# MainSocket.net
KiCad netlist of a schematic drawn in Altium Designer
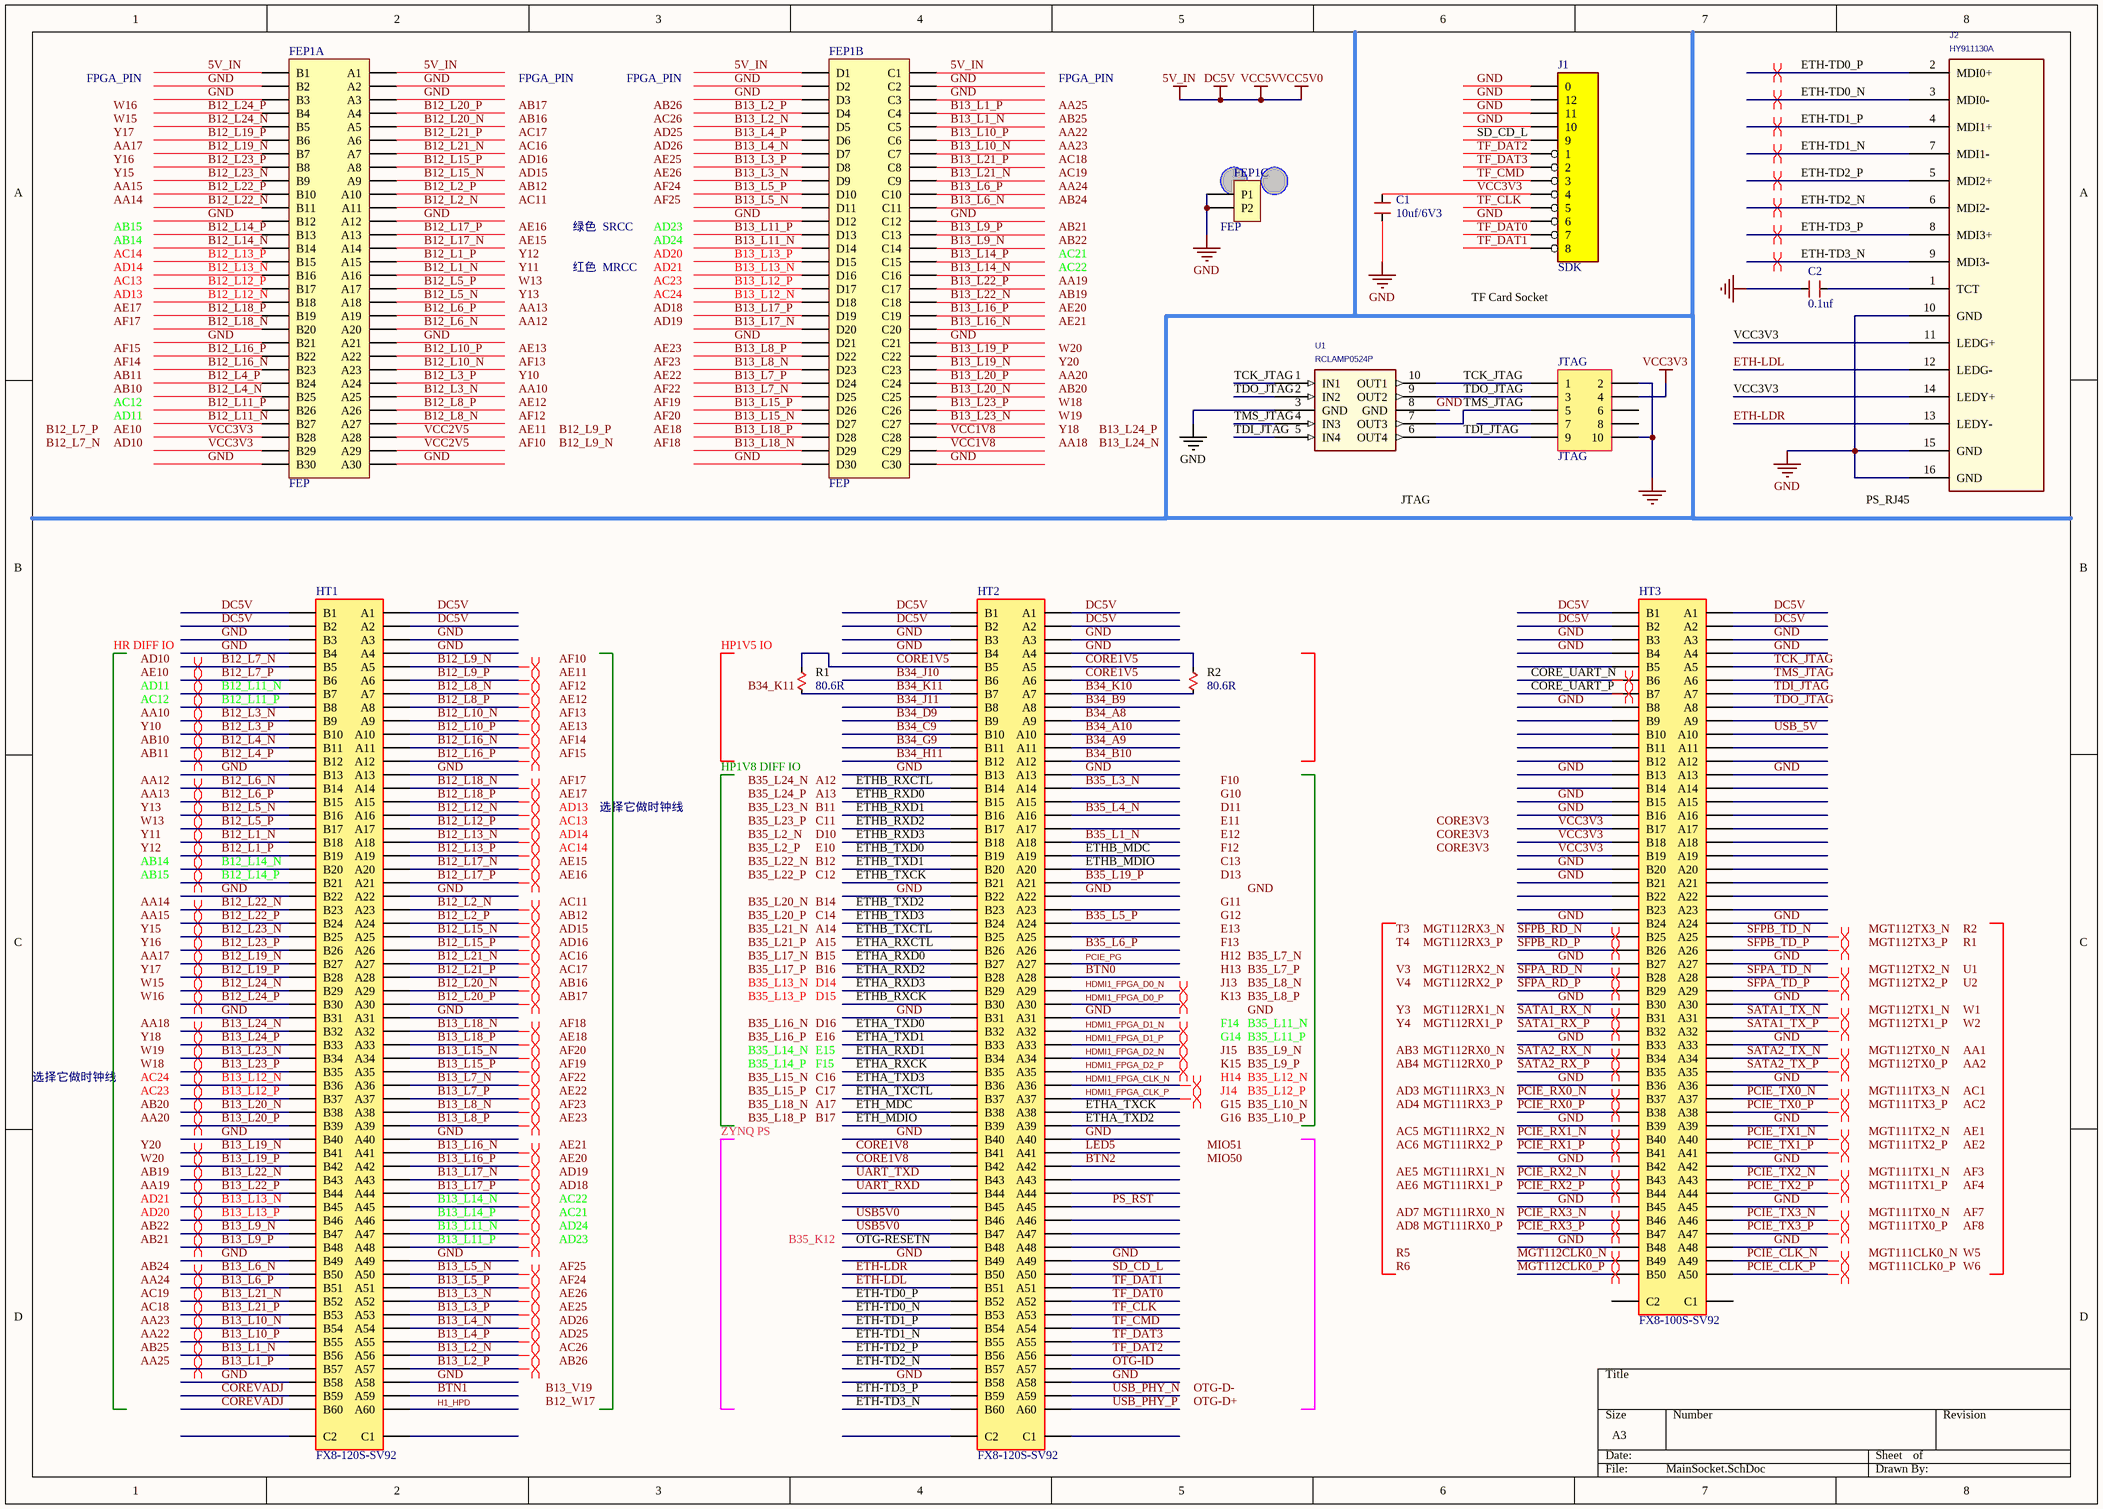
[diagram p0: MainSocket.SchDoc]

(export (version "E")
  (design (tool "Eeschema 10.0.6"))
  (components
    (comp (ref "C1")
      (value "10uf/6V3")
      (footprint "CAP0603")
      (description "Generic Capacitor")
      (libsource (lib "Digilent") (part "CAPACITOR"))
    )
    (comp (ref "C2")
      (value "0.1uf")
      (footprint "CAP0402")
      (description "Generic Capacitor")
      (libsource (lib "Miz701_fun20160215") (part "CAPACITOR"))
    )
    (comp (ref "FEP1") (value "FEP") (footprint "FEP-X2") (libsource (lib "") (part "FEP-2X_1")))
    (comp (ref "HT1")
      (value "FX8-120S-SV92")
      (footprint "FX8-120S-SV92")
      (libsource (lib "MIZ7035") (part "FX8-120P-SV92"))
    )
    (comp (ref "HT2")
      (value "FX8-120S-SV92")
      (footprint "FX8-120S-SV92")
      (libsource (lib "MIZ7035") (part "FX8-120P-SV92"))
    )
    (comp (ref "HT3")
      (value "FX8-100S-SV92")
      (footprint "FX8-100S-SV92")
      (libsource (lib "MIZ7035") (part "FX8-100P-SV92"))
    )
    (comp (ref "J1") (value "SDK") (footprint "TF_K") (libsource (lib "jinrylib") (part "SD")))
    (comp (ref "J2") (value "HY911130A") (footprint "HY911130A") (libsource (lib "*") (part "HY911130A")))
    (comp (ref "JTAG")
      (value "JTAG")
      (footprint "HEADER5X2X2.0T")
      (libsource (lib "mis607") (part "HEADER2X5"))
    )
    (comp (ref "R1")
      (value "80.6R")
      (footprint "RES0402")
      (description "Generic Resistor")
      (libsource (lib "MIZ7035_定制") (part "RESISTOR"))
    )
    (comp (ref "R2")
      (value "80.6R")
      (footprint "RES0402")
      (description "Generic Resistor")
      (libsource (lib "MIZ7035_定制") (part "RESISTOR"))
    )
    (comp (ref "U1")
      (value "RCLAMP0524P")
      (footprint "SLP2510P8_10")
      (libsource (lib "*") (part "RCLAMP0524P"))
    )
  )
  (nets
    (net (code "109") (name "/B12_L1_N") (class "Default")
      (node (ref "FEP1") (pin "A16") (pinfunction "A16_A16") (pintype "passive"))
      (node (ref "HT1") (pin "B18") (pinfunction "B18_B18") (pintype "passive"))
    )
    (net (code "110") (name "/B12_L1_P") (class "Default")
      (node (ref "FEP1") (pin "A15") (pinfunction "A15_A15") (pintype "passive"))
      (node (ref "HT1") (pin "B19") (pinfunction "B19_B19") (pintype "passive"))
    )
    (net (code "111") (name "/B12_L2_N") (class "Default")
      (node (ref "FEP1") (pin "A11") (pinfunction "A11_A11") (pintype "passive"))
      (node (ref "HT1") (pin "A23") (pinfunction "A23_A23") (pintype "passive"))
    )
    (net (code "112") (name "/B12_L2_P") (class "Default")
      (node (ref "FEP1") (pin "A10") (pinfunction "A10_A10") (pintype "passive"))
      (node (ref "HT1") (pin "A24") (pinfunction "A24_A24") (pintype "passive"))
    )
    (net (code "113") (name "/B12_L3_N") (class "Default")
      (node (ref "FEP1") (pin "A25") (pinfunction "A25_A25") (pintype "passive"))
      (node (ref "HT1") (pin "B9") (pinfunction "B9_B9") (pintype "passive"))
    )
    (net (code "114") (name "/B12_L3_P") (class "Default")
      (node (ref "FEP1") (pin "A24") (pinfunction "A24_A24") (pintype "passive"))
      (node (ref "HT1") (pin "B10") (pinfunction "B10_B10") (pintype "passive"))
    )
    (net (code "115") (name "/B12_L4_N") (class "Default")
      (node (ref "FEP1") (pin "B25") (pinfunction "B25_B25") (pintype "passive"))
      (node (ref "HT1") (pin "B11") (pinfunction "B11_B11") (pintype "passive"))
    )
    (net (code "116") (name "/B12_L4_P") (class "Default")
      (node (ref "FEP1") (pin "B24") (pinfunction "B24_B24") (pintype "passive"))
      (node (ref "HT1") (pin "B12") (pinfunction "B12_B12") (pintype "passive"))
    )
    (net (code "117") (name "/B12_L5_N") (class "Default")
      (node (ref "FEP1") (pin "A18") (pinfunction "A18_A18") (pintype "passive"))
      (node (ref "HT1") (pin "B16") (pinfunction "B16_B16") (pintype "passive"))
    )
    (net (code "118") (name "/B12_L5_P") (class "Default")
      (node (ref "FEP1") (pin "A17") (pinfunction "A17_A17") (pintype "passive"))
      (node (ref "HT1") (pin "B17") (pinfunction "B17_B17") (pintype "passive"))
    )
    (net (code "119") (name "/B12_L6_N") (class "Default")
      (node (ref "FEP1") (pin "A20") (pinfunction "A20_A20") (pintype "passive"))
      (node (ref "HT1") (pin "B14") (pinfunction "B14_B14") (pintype "passive"))
    )
    (net (code "120") (name "/B12_L6_P") (class "Default")
      (node (ref "FEP1") (pin "A19") (pinfunction "A19_A19") (pintype "passive"))
      (node (ref "HT1") (pin "B15") (pinfunction "B15_B15") (pintype "passive"))
    )
    (net (code "121") (name "/B12_L7_N") (class "Default")
      (node (ref "HT1") (pin "B5") (pinfunction "B5_B5") (pintype "passive"))
    )
    (net (code "122") (name "/B12_L7_P") (class "Default")
      (node (ref "HT1") (pin "B6") (pinfunction "B6_B6") (pintype "passive"))
    )
    (net (code "123") (name "/B12_L8_N") (class "Default")
      (node (ref "FEP1") (pin "A27") (pinfunction "A27_A27") (pintype "passive"))
      (node (ref "HT1") (pin "A7") (pinfunction "A7_A7") (pintype "passive"))
    )
    (net (code "124") (name "/B12_L8_P") (class "Default")
      (node (ref "FEP1") (pin "A26") (pinfunction "A26_A26") (pintype "passive"))
      (node (ref "HT1") (pin "A8") (pinfunction "A8_A8") (pintype "passive"))
    )
    (net (code "125") (name "/B12_L9_N") (class "Default")
      (node (ref "HT1") (pin "A5") (pinfunction "A5_A5") (pintype "passive"))
    )
    (net (code "126") (name "/B12_L9_P") (class "Default")
      (node (ref "HT1") (pin "A6") (pinfunction "A6_A6") (pintype "passive"))
    )
    (net (code "127") (name "/B12_L10_N") (class "Default")
      (node (ref "FEP1") (pin "A23") (pinfunction "A23_A23") (pintype "passive"))
      (node (ref "HT1") (pin "A9") (pinfunction "A9_A9") (pintype "passive"))
    )
    (net (code "128") (name "/B12_L10_P") (class "Default")
      (node (ref "FEP1") (pin "A22") (pinfunction "A22_A22") (pintype "passive"))
      (node (ref "HT1") (pin "A10") (pinfunction "A10_A10") (pintype "passive"))
    )
    (net (code "129") (name "/B12_L11_N") (class "Default")
      (node (ref "FEP1") (pin "B27") (pinfunction "B27_B27") (pintype "passive"))
      (node (ref "HT1") (pin "B7") (pinfunction "B7_B7") (pintype "passive"))
    )
    (net (code "130") (name "/B12_L11_P") (class "Default")
      (node (ref "FEP1") (pin "B26") (pinfunction "B26_B26") (pintype "passive"))
      (node (ref "HT1") (pin "B8") (pinfunction "B8_B8") (pintype "passive"))
    )
    (net (code "131") (name "/B12_L12_N") (class "Default")
      (node (ref "FEP1") (pin "B18") (pinfunction "B18_B18") (pintype "passive"))
      (node (ref "HT1") (pin "A16") (pinfunction "A16_A16") (pintype "passive"))
    )
    (net (code "132") (name "/B12_L12_P") (class "Default")
      (node (ref "FEP1") (pin "B17") (pinfunction "B17_B17") (pintype "passive"))
      (node (ref "HT1") (pin "A17") (pinfunction "A17_A17") (pintype "passive"))
    )
    (net (code "133") (name "/B12_L13_N") (class "Default")
      (node (ref "FEP1") (pin "B16") (pinfunction "B16_B16") (pintype "passive"))
      (node (ref "HT1") (pin "A18") (pinfunction "A18_A18") (pintype "passive"))
    )
    (net (code "134") (name "/B12_L13_P") (class "Default")
      (node (ref "FEP1") (pin "B15") (pinfunction "B15_B15") (pintype "passive"))
      (node (ref "HT1") (pin "A19") (pinfunction "A19_A19") (pintype "passive"))
    )
    (net (code "135") (name "/B12_L14_N") (class "Default")
      (node (ref "FEP1") (pin "B14") (pinfunction "B14_B14") (pintype "passive"))
      (node (ref "HT1") (pin "B20") (pinfunction "B20_B20") (pintype "passive"))
    )
    (net (code "136") (name "/B12_L14_P") (class "Default")
      (node (ref "FEP1") (pin "B13") (pinfunction "B13_B13") (pintype "passive"))
      (node (ref "HT1") (pin "B21") (pinfunction "B21_B21") (pintype "passive"))
    )
    (net (code "137") (name "/B12_L15_N") (class "Default")
      (node (ref "FEP1") (pin "A9") (pinfunction "A9_A9") (pintype "passive"))
      (node (ref "HT1") (pin "A25") (pinfunction "A25_A25") (pintype "passive"))
    )
    (net (code "138") (name "/B12_L15_P") (class "Default")
      (node (ref "FEP1") (pin "A8") (pinfunction "A8_A8") (pintype "passive"))
      (node (ref "HT1") (pin "A26") (pinfunction "A26_A26") (pintype "passive"))
    )
    (net (code "139") (name "/B12_L16_N") (class "Default")
      (node (ref "FEP1") (pin "B23") (pinfunction "B23_B23") (pintype "passive"))
      (node (ref "HT1") (pin "A11") (pinfunction "A11_A11") (pintype "passive"))
    )
    (net (code "140") (name "/B12_L16_P") (class "Default")
      (node (ref "FEP1") (pin "B22") (pinfunction "B22_B22") (pintype "passive"))
      (node (ref "HT1") (pin "A12") (pinfunction "A12_A12") (pintype "passive"))
    )
    (net (code "141") (name "/B12_L17_N") (class "Default")
      (node (ref "FEP1") (pin "A14") (pinfunction "A14_A14") (pintype "passive"))
      (node (ref "HT1") (pin "A20") (pinfunction "A20_A20") (pintype "passive"))
    )
    (net (code "142") (name "/B12_L17_P") (class "Default")
      (node (ref "FEP1") (pin "A13") (pinfunction "A13_A13") (pintype "passive"))
      (node (ref "HT1") (pin "A21") (pinfunction "A21_A21") (pintype "passive"))
    )
    (net (code "143") (name "/B12_L18_N") (class "Default")
      (node (ref "FEP1") (pin "B20") (pinfunction "B20_B20") (pintype "passive"))
      (node (ref "HT1") (pin "A14") (pinfunction "A14_A14") (pintype "passive"))
    )
    (net (code "144") (name "/B12_L18_P") (class "Default")
      (node (ref "FEP1") (pin "B19") (pinfunction "B19_B19") (pintype "passive"))
      (node (ref "HT1") (pin "A15") (pinfunction "A15_A15") (pintype "passive"))
    )
    (net (code "145") (name "/B12_L19_N") (class "Default")
      (node (ref "FEP1") (pin "B7") (pinfunction "B7_B7") (pintype "passive"))
      (node (ref "HT1") (pin "B27") (pinfunction "B27_B27") (pintype "passive"))
    )
    (net (code "146") (name "/B12_L19_P") (class "Default")
      (node (ref "FEP1") (pin "B6") (pinfunction "B6_B6") (pintype "passive"))
      (node (ref "HT1") (pin "B28") (pinfunction "B28_B28") (pintype "passive"))
    )
    (net (code "147") (name "/B12_L20_N") (class "Default")
      (node (ref "FEP1") (pin "A5") (pinfunction "A5_A5") (pintype "passive"))
      (node (ref "HT1") (pin "A29") (pinfunction "A29_A29") (pintype "passive"))
    )
    (net (code "148") (name "/B12_L20_P") (class "Default")
      (node (ref "FEP1") (pin "A4") (pinfunction "A4_A4") (pintype "passive"))
      (node (ref "HT1") (pin "A30") (pinfunction "A30_A30") (pintype "passive"))
    )
    (net (code "149") (name "/B12_L21_N") (class "Default")
      (node (ref "FEP1") (pin "A7") (pinfunction "A7_A7") (pintype "passive"))
      (node (ref "HT1") (pin "A27") (pinfunction "A27_A27") (pintype "passive"))
    )
    (net (code "150") (name "/B12_L21_P") (class "Default")
      (node (ref "FEP1") (pin "A6") (pinfunction "A6_A6") (pintype "passive"))
      (node (ref "HT1") (pin "A28") (pinfunction "A28_A28") (pintype "passive"))
    )
    (net (code "151") (name "/B12_L22_N") (class "Default")
      (node (ref "FEP1") (pin "B11") (pinfunction "B11_B11") (pintype "passive"))
      (node (ref "HT1") (pin "B23") (pinfunction "B23_B23") (pintype "passive"))
    )
    (net (code "152") (name "/B12_L22_P") (class "Default")
      (node (ref "FEP1") (pin "B10") (pinfunction "B10_B10") (pintype "passive"))
      (node (ref "HT1") (pin "B24") (pinfunction "B24_B24") (pintype "passive"))
    )
    (net (code "153") (name "/B12_L23_N") (class "Default")
      (node (ref "FEP1") (pin "B9") (pinfunction "B9_B9") (pintype "passive"))
      (node (ref "HT1") (pin "B25") (pinfunction "B25_B25") (pintype "passive"))
    )
    (net (code "154") (name "/B12_L23_P") (class "Default")
      (node (ref "FEP1") (pin "B8") (pinfunction "B8_B8") (pintype "passive"))
      (node (ref "HT1") (pin "B26") (pinfunction "B26_B26") (pintype "passive"))
    )
    (net (code "155") (name "/B12_L24_N") (class "Default")
      (node (ref "FEP1") (pin "B5") (pinfunction "B5_B5") (pintype "passive"))
      (node (ref "HT1") (pin "B29") (pinfunction "B29_B29") (pintype "passive"))
    )
    (net (code "156") (name "/B12_L24_P") (class "Default")
      (node (ref "FEP1") (pin "B4") (pinfunction "B4_B4") (pintype "passive"))
      (node (ref "HT1") (pin "B30") (pinfunction "B30_B30") (pintype "passive"))
    )
    (net (code "158") (name "/B13_L1_N") (class "Default")
      (node (ref "FEP1") (pin "C5") (pinfunction "C5_C5") (pintype "passive"))
      (node (ref "HT1") (pin "B56") (pinfunction "B56_B56") (pintype "passive"))
    )
    (net (code "159") (name "/B13_L1_P") (class "Default")
      (node (ref "FEP1") (pin "C4") (pinfunction "C4_C4") (pintype "passive"))
      (node (ref "HT1") (pin "B57") (pinfunction "B57_B57") (pintype "passive"))
    )
    (net (code "160") (name "/B13_L2_N") (class "Default")
      (node (ref "FEP1") (pin "D5") (pinfunction "D5_D5") (pintype "passive"))
      (node (ref "HT1") (pin "A56") (pinfunction "A56_A56") (pintype "passive"))
    )
    (net (code "161") (name "/B13_L2_P") (class "Default")
      (node (ref "FEP1") (pin "D4") (pinfunction "D4_D4") (pintype "passive"))
      (node (ref "HT1") (pin "A57") (pinfunction "A57_A57") (pintype "passive"))
    )
    (net (code "162") (name "/B13_L3_N") (class "Default")
      (node (ref "FEP1") (pin "D9") (pinfunction "D9_D9") (pintype "passive"))
      (node (ref "HT1") (pin "A52") (pinfunction "A52_A52") (pintype "passive"))
    )
    (net (code "163") (name "/B13_L3_P") (class "Default")
      (node (ref "FEP1") (pin "D8") (pinfunction "D8_D8") (pintype "passive"))
      (node (ref "HT1") (pin "A53") (pinfunction "A53_A53") (pintype "passive"))
    )
    (net (code "164") (name "/B13_L4_N") (class "Default")
      (node (ref "FEP1") (pin "D7") (pinfunction "D7_D7") (pintype "passive"))
      (node (ref "HT1") (pin "A54") (pinfunction "A54_A54") (pintype "passive"))
    )
    (net (code "165") (name "/B13_L4_P") (class "Default")
      (node (ref "FEP1") (pin "D6") (pinfunction "D6_D6") (pintype "passive"))
      (node (ref "HT1") (pin "A55") (pinfunction "A55_A55") (pintype "passive"))
    )
    (net (code "166") (name "/B13_L5_N") (class "Default")
      (node (ref "FEP1") (pin "D11") (pinfunction "D11_D11") (pintype "passive"))
      (node (ref "HT1") (pin "A50") (pinfunction "A50_A50") (pintype "passive"))
    )
    (net (code "167") (name "/B13_L5_P") (class "Default")
      (node (ref "FEP1") (pin "D10") (pinfunction "D10_D10") (pintype "passive"))
      (node (ref "HT1") (pin "A51") (pinfunction "A51_A51") (pintype "passive"))
    )
    (net (code "168") (name "/B13_L6_N") (class "Default")
      (node (ref "FEP1") (pin "C11") (pinfunction "C11_C11") (pintype "passive"))
      (node (ref "HT1") (pin "B50") (pinfunction "B50_B50") (pintype "passive"))
    )
    (net (code "169") (name "/B13_L6_P") (class "Default")
      (node (ref "FEP1") (pin "C10") (pinfunction "C10_C10") (pintype "passive"))
      (node (ref "HT1") (pin "B51") (pinfunction "B51_B51") (pintype "passive"))
    )
    (net (code "170") (name "/B13_L7_N") (class "Default")
      (node (ref "FEP1") (pin "D25") (pinfunction "D25_D25") (pintype "passive"))
      (node (ref "HT1") (pin "A36") (pinfunction "A36_A36") (pintype "passive"))
    )
    (net (code "171") (name "/B13_L7_P") (class "Default")
      (node (ref "FEP1") (pin "D24") (pinfunction "D24_D24") (pintype "passive"))
      (node (ref "HT1") (pin "A37") (pinfunction "A37_A37") (pintype "passive"))
    )
    (net (code "172") (name "/B13_L8_N") (class "Default")
      (node (ref "FEP1") (pin "D23") (pinfunction "D23_D23") (pintype "passive"))
      (node (ref "HT1") (pin "A38") (pinfunction "A38_A38") (pintype "passive"))
    )
    (net (code "173") (name "/B13_L8_P") (class "Default")
      (node (ref "FEP1") (pin "D22") (pinfunction "D22_D22") (pintype "passive"))
      (node (ref "HT1") (pin "A39") (pinfunction "A39_A39") (pintype "passive"))
    )
    (net (code "174") (name "/B13_L9_N") (class "Default")
      (node (ref "FEP1") (pin "C14") (pinfunction "C14_C14") (pintype "passive"))
      (node (ref "HT1") (pin "B47") (pinfunction "B47_B47") (pintype "passive"))
    )
    (net (code "175") (name "/B13_L9_P") (class "Default")
      (node (ref "FEP1") (pin "C13") (pinfunction "C13_C13") (pintype "passive"))
      (node (ref "HT1") (pin "B48") (pinfunction "B48_B48") (pintype "passive"))
    )
    (net (code "176") (name "/B13_L10_N") (class "Default")
      (node (ref "FEP1") (pin "C7") (pinfunction "C7_C7") (pintype "passive"))
      (node (ref "HT1") (pin "B54") (pinfunction "B54_B54") (pintype "passive"))
    )
    (net (code "177") (name "/B13_L10_P") (class "Default")
      (node (ref "FEP1") (pin "C6") (pinfunction "C6_C6") (pintype "passive"))
      (node (ref "HT1") (pin "B55") (pinfunction "B55_B55") (pintype "passive"))
    )
    (net (code "178") (name "/B13_L11_N") (class "Default")
      (node (ref "FEP1") (pin "D14") (pinfunction "D14_D14") (pintype "passive"))
      (node (ref "HT1") (pin "A47") (pinfunction "A47_A47") (pintype "passive"))
    )
    (net (code "179") (name "/B13_L11_P") (class "Default")
      (node (ref "FEP1") (pin "D13") (pinfunction "D13_D13") (pintype "passive"))
      (node (ref "HT1") (pin "A48") (pinfunction "A48_A48") (pintype "passive"))
    )
    (net (code "180") (name "/B13_L12_N") (class "Default")
      (node (ref "FEP1") (pin "D18") (pinfunction "D18_D18") (pintype "passive"))
      (node (ref "HT1") (pin "B36") (pinfunction "B36_B36") (pintype "passive"))
    )
    (net (code "181") (name "/B13_L12_P") (class "Default")
      (node (ref "FEP1") (pin "D17") (pinfunction "D17_D17") (pintype "passive"))
      (node (ref "HT1") (pin "B37") (pinfunction "B37_B37") (pintype "passive"))
    )
    (net (code "182") (name "/B13_L13_N") (class "Default")
      (node (ref "FEP1") (pin "D16") (pinfunction "D16_D16") (pintype "passive"))
      (node (ref "HT1") (pin "B45") (pinfunction "B45_B45") (pintype "passive"))
    )
    (net (code "183") (name "/B13_L13_P") (class "Default")
      (node (ref "FEP1") (pin "D15") (pinfunction "D15_D15") (pintype "passive"))
      (node (ref "HT1") (pin "B46") (pinfunction "B46_B46") (pintype "passive"))
    )
    (net (code "184") (name "/B13_L14_N") (class "Default")
      (node (ref "FEP1") (pin "C16") (pinfunction "C16_C16") (pintype "passive"))
      (node (ref "HT1") (pin "A45") (pinfunction "A45_A45") (pintype "passive"))
    )
    (net (code "185") (name "/B13_L14_P") (class "Default")
      (node (ref "FEP1") (pin "C15") (pinfunction "C15_C15") (pintype "passive"))
      (node (ref "HT1") (pin "A46") (pinfunction "A46_A46") (pintype "passive"))
    )
    (net (code "186") (name "/B13_L15_N") (class "Default")
      (node (ref "FEP1") (pin "D27") (pinfunction "D27_D27") (pintype "passive"))
      (node (ref "HT1") (pin "A34") (pinfunction "A34_A34") (pintype "passive"))
    )
    (net (code "187") (name "/B13_L15_P") (class "Default")
      (node (ref "FEP1") (pin "D26") (pinfunction "D26_D26") (pintype "passive"))
      (node (ref "HT1") (pin "A35") (pinfunction "A35_A35") (pintype "passive"))
    )
    (net (code "188") (name "/B13_L16_N") (class "Default")
      (node (ref "FEP1") (pin "C20") (pinfunction "C20_C20") (pintype "passive"))
      (node (ref "HT1") (pin "A41") (pinfunction "A41_A41") (pintype "passive"))
    )
    (net (code "189") (name "/B13_L16_P") (class "Default")
      (node (ref "FEP1") (pin "C19") (pinfunction "C19_C19") (pintype "passive"))
      (node (ref "HT1") (pin "A42") (pinfunction "A42_A42") (pintype "passive"))
    )
    (net (code "190") (name "/B13_L17_N") (class "Default")
      (node (ref "FEP1") (pin "D20") (pinfunction "D20_D20") (pintype "passive"))
      (node (ref "HT1") (pin "A43") (pinfunction "A43_A43") (pintype "passive"))
    )
    (net (code "191") (name "/B13_L17_P") (class "Default")
      (node (ref "FEP1") (pin "D19") (pinfunction "D19_D19") (pintype "passive"))
      (node (ref "HT1") (pin "A44") (pinfunction "A44_A44") (pintype "passive"))
    )
    (net (code "192") (name "/B13_L18_N") (class "Default")
      (node (ref "FEP1") (pin "D29") (pinfunction "D29_D29") (pintype "passive"))
      (node (ref "HT1") (pin "A32") (pinfunction "A32_A32") (pintype "passive"))
    )
    (net (code "193") (name "/B13_L18_P") (class "Default")
      (node (ref "FEP1") (pin "D28") (pinfunction "D28_D28") (pintype "passive"))
      (node (ref "HT1") (pin "A33") (pinfunction "A33_A33") (pintype "passive"))
    )
    (net (code "194") (name "/B13_L19_N") (class "Default")
      (node (ref "FEP1") (pin "C23") (pinfunction "C23_C23") (pintype "passive"))
      (node (ref "HT1") (pin "B41") (pinfunction "B41_B41") (pintype "passive"))
    )
    (net (code "195") (name "/B13_L19_P") (class "Default")
      (node (ref "FEP1") (pin "C22") (pinfunction "C22_C22") (pintype "passive"))
      (node (ref "HT1") (pin "B42") (pinfunction "B42_B42") (pintype "passive"))
    )
    (net (code "196") (name "/B13_L20_N") (class "Default")
      (node (ref "FEP1") (pin "C25") (pinfunction "C25_C25") (pintype "passive"))
      (node (ref "HT1") (pin "B38") (pinfunction "B38_B38") (pintype "passive"))
    )
    (net (code "197") (name "/B13_L20_P") (class "Default")
      (node (ref "FEP1") (pin "C24") (pinfunction "C24_C24") (pintype "passive"))
      (node (ref "HT1") (pin "B39") (pinfunction "B39_B39") (pintype "passive"))
    )
    (net (code "198") (name "/B13_L21_N") (class "Default")
      (node (ref "FEP1") (pin "C9") (pinfunction "C9_C9") (pintype "passive"))
      (node (ref "HT1") (pin "B52") (pinfunction "B52_B52") (pintype "passive"))
    )
    (net (code "199") (name "/B13_L21_P") (class "Default")
      (node (ref "FEP1") (pin "C8") (pinfunction "C8_C8") (pintype "passive"))
      (node (ref "HT1") (pin "B53") (pinfunction "B53_B53") (pintype "passive"))
    )
    (net (code "200") (name "/B13_L22_N") (class "Default")
      (node (ref "FEP1") (pin "C18") (pinfunction "C18_C18") (pintype "passive"))
      (node (ref "HT1") (pin "B43") (pinfunction "B43_B43") (pintype "passive"))
    )
    (net (code "201") (name "/B13_L22_P") (class "Default")
      (node (ref "FEP1") (pin "C17") (pinfunction "C17_C17") (pintype "passive"))
      (node (ref "HT1") (pin "B44") (pinfunction "B44_B44") (pintype "passive"))
    )
    (net (code "202") (name "/B13_L23_N") (class "Default")
      (node (ref "FEP1") (pin "C27") (pinfunction "C27_C27") (pintype "passive"))
      (node (ref "HT1") (pin "B34") (pinfunction "B34_B34") (pintype "passive"))
    )
    (net (code "203") (name "/B13_L23_P") (class "Default")
      (node (ref "FEP1") (pin "C26") (pinfunction "C26_C26") (pintype "passive"))
      (node (ref "HT1") (pin "B35") (pinfunction "B35_B35") (pintype "passive"))
    )
    (net (code "204") (name "/B13_L24_N") (class "Default")
      (node (ref "HT1") (pin "B32") (pinfunction "B32_B32") (pintype "passive"))
    )
    (net (code "205") (name "/B13_L24_P") (class "Default")
      (node (ref "HT1") (pin "B33") (pinfunction "B33_B33") (pintype "passive"))
    )
    (net (code "211") (name "/B34_A8") (class "Default")
      (node (ref "HT2") (pin "A9") (pinfunction "A9_A9") (pintype "passive"))
    )
    (net (code "212") (name "/B34_A9") (class "Default")
      (node (ref "HT2") (pin "A11") (pinfunction "A11_A11") (pintype "passive"))
    )
    (net (code "213") (name "/B34_A10") (class "Default")
      (node (ref "HT2") (pin "A10") (pinfunction "A10_A10") (pintype "passive"))
    )
    (net (code "214") (name "/B34_B9") (class "Default")
      (node (ref "HT2") (pin "A8") (pinfunction "A8_A8") (pintype "passive"))
    )
    (net (code "215") (name "/B34_B10") (class "Default")
      (node (ref "HT2") (pin "A12") (pinfunction "A12_A12") (pintype "passive"))
    )
    (net (code "216") (name "/B34_C9") (class "Default")
      (node (ref "HT2") (pin "B10") (pinfunction "B10_B10") (pintype "passive"))
    )
    (net (code "217") (name "/B34_D9") (class "Default")
      (node (ref "HT2") (pin "B9") (pinfunction "B9_B9") (pintype "passive"))
    )
    (net (code "218") (name "/B34_G9") (class "Default")
      (node (ref "HT2") (pin "B11") (pinfunction "B11_B11") (pintype "passive"))
    )
    (net (code "219") (name "/B34_H11") (class "Default")
      (node (ref "HT2") (pin "B12") (pinfunction "B12_B12") (pintype "passive"))
    )
    (net (code "220") (name "/B34_J10") (class "Default")
      (node (ref "HT2") (pin "B6") (pinfunction "B6_B6") (pintype "passive"))
    )
    (net (code "221") (name "/B34_J11") (class "Default")
      (node (ref "HT2") (pin "B8") (pinfunction "B8_B8") (pintype "passive"))
    )
    (net (code "222") (name "/B34_K10") (class "Default")
      (node (ref "HT2") (pin "A7") (pinfunction "A7_A7") (pintype "passive"))
      (node (ref "R2") (pin "1") (pinfunction "1_1") (pintype "passive"))
    )
    (net (code "223") (name "/B34_K11") (class "Default")
      (node (ref "HT2") (pin "B7") (pinfunction "B7_B7") (pintype "passive"))
      (node (ref "R1") (pin "1") (pinfunction "1_1") (pintype "passive"))
    )
    (net (code "225") (name "/B35_L1_N") (class "Default")
      (node (ref "HT2") (pin "A18") (pinfunction "A18_A18") (pintype "passive"))
    )
    (net (code "228") (name "/B35_L3_N") (class "Default")
      (node (ref "HT2") (pin "A14") (pinfunction "A14_A14") (pintype "passive"))
    )
    (net (code "229") (name "/B35_L4_N") (class "Default")
      (node (ref "HT2") (pin "A16") (pinfunction "A16_A16") (pintype "passive"))
    )
    (net (code "230") (name "/B35_L5_P") (class "Default")
      (node (ref "HT2") (pin "A24") (pinfunction "A24_A24") (pintype "passive"))
    )
    (net (code "231") (name "/B35_L6_P") (class "Default")
      (node (ref "HT2") (pin "A26") (pinfunction "A26_A26") (pintype "passive"))
    )
    (net (code "256") (name "/B35_L19_P") (class "Default")
      (node (ref "HT2") (pin "A21") (pinfunction "A21_A21") (pintype "passive"))
    )
    (net (code "267") (name "/BTN0") (class "Default")
      (node (ref "HT2") (pin "A28") (pinfunction "A28_A28") (pintype "passive"))
    )
    (net (code "268") (name "/BTN1") (class "Default")
      (node (ref "HT1") (pin "A59") (pinfunction "A59_A59") (pintype "passive"))
    )
    (net (code "269") (name "/BTN2") (class "Default")
      (node (ref "HT2") (pin "A42") (pinfunction "A42_A42") (pintype "passive"))
    )
    (net (code "276") (name "/CORE1V5") (class "Default")
      (node (ref "HT2") (pin "A5") (pinfunction "A5_A5") (pintype "passive"))
      (node (ref "HT2") (pin "A6") (pinfunction "A6_A6") (pintype "passive"))
      (node (ref "HT2") (pin "B5") (pinfunction "B5_B5") (pintype "passive"))
      (node (ref "R1") (pin "2") (pinfunction "2_2") (pintype "passive"))
    )
    (net (code "277") (name "/CORE1V8") (class "Default")
      (node (ref "HT2") (pin "B41") (pinfunction "B41_B41") (pintype "passive"))
      (node (ref "HT2") (pin "B42") (pinfunction "B42_B42") (pintype "passive"))
    )
    (net (code "279") (name "/COREVADJ") (class "Default")
      (node (ref "HT1") (pin "B59") (pinfunction "B59_B59") (pintype "passive"))
      (node (ref "HT1") (pin "B60") (pinfunction "B60_B60") (pintype "passive"))
    )
    (net (code "280") (name "/CORE_UART_N") (class "Default")
      (node (ref "HT3") (pin "B6") (pinfunction "B6_B6") (pintype "passive"))
    )
    (net (code "281") (name "/CORE_UART_P") (class "Default")
      (node (ref "HT3") (pin "B7") (pinfunction "B7_B7") (pintype "passive"))
    )
    (net (code "294") (name "/ETH-LDL") (class "Default")
      (node (ref "HT2") (pin "B51") (pinfunction "B51_B51") (pintype "passive"))
      (node (ref "J2") (pin "12") (pinfunction "LEDG-_12") (pintype "passive"))
    )
    (net (code "295") (name "/ETH-LDR") (class "Default")
      (node (ref "HT2") (pin "B50") (pinfunction "B50_B50") (pintype "passive"))
      (node (ref "J2") (pin "13") (pinfunction "LEDY-_13") (pintype "passive"))
    )
    (net (code "296") (name "/ETH-TD0_N") (class "Default")
      (node (ref "HT2") (pin "B53") (pinfunction "B53_B53") (pintype "passive"))
      (node (ref "J2") (pin "3") (pinfunction "MDI0-_3") (pintype "passive"))
    )
    (net (code "297") (name "/ETH-TD0_P") (class "Default")
      (node (ref "HT2") (pin "B52") (pinfunction "B52_B52") (pintype "passive"))
      (node (ref "J2") (pin "2") (pinfunction "MDI0+_2") (pintype "passive"))
    )
    (net (code "298") (name "/ETH-TD1_N") (class "Default")
      (node (ref "HT2") (pin "B55") (pinfunction "B55_B55") (pintype "passive"))
      (node (ref "J2") (pin "7") (pinfunction "MDI1-_7") (pintype "passive"))
    )
    (net (code "299") (name "/ETH-TD1_P") (class "Default")
      (node (ref "HT2") (pin "B54") (pinfunction "B54_B54") (pintype "passive"))
      (node (ref "J2") (pin "4") (pinfunction "MDI1+_4") (pintype "passive"))
    )
    (net (code "300") (name "/ETH-TD2_N") (class "Default")
      (node (ref "HT2") (pin "B57") (pinfunction "B57_B57") (pintype "passive"))
      (node (ref "J2") (pin "6") (pinfunction "MDI2-_6") (pintype "passive"))
    )
    (net (code "301") (name "/ETH-TD2_P") (class "Default")
      (node (ref "HT2") (pin "B56") (pinfunction "B56_B56") (pintype "passive"))
      (node (ref "J2") (pin "5") (pinfunction "MDI2+_5") (pintype "passive"))
    )
    (net (code "302") (name "/ETH-TD3_N") (class "Default")
      (node (ref "HT2") (pin "B60") (pinfunction "B60_B60") (pintype "passive"))
      (node (ref "J2") (pin "9") (pinfunction "MDI3-_9") (pintype "passive"))
    )
    (net (code "303") (name "/ETH-TD3_P") (class "Default")
      (node (ref "HT2") (pin "B59") (pinfunction "B59_B59") (pintype "passive"))
      (node (ref "J2") (pin "8") (pinfunction "MDI3+_8") (pintype "passive"))
    )
    (net (code "304") (name "/ETHA_RXCK") (class "Default")
      (node (ref "HT2") (pin "B35") (pinfunction "B35_B35") (pintype "passive"))
    )
    (net (code "305") (name "/ETHA_RXCTL") (class "Default")
      (node (ref "HT2") (pin "B26") (pinfunction "B26_B26") (pintype "passive"))
    )
    (net (code "306") (name "/ETHA_RXD0") (class "Default")
      (node (ref "HT2") (pin "B27") (pinfunction "B27_B27") (pintype "passive"))
    )
    (net (code "307") (name "/ETHA_RXD1") (class "Default")
      (node (ref "HT2") (pin "B34") (pinfunction "B34_B34") (pintype "passive"))
    )
    (net (code "308") (name "/ETHA_RXD2") (class "Default")
      (node (ref "HT2") (pin "B28") (pinfunction "B28_B28") (pintype "passive"))
    )
    (net (code "309") (name "/ETHA_RXD3") (class "Default")
      (node (ref "HT2") (pin "B29") (pinfunction "B29_B29") (pintype "passive"))
    )
    (net (code "310") (name "/ETHA_TXCK") (class "Default")
      (node (ref "HT2") (pin "A38") (pinfunction "A38_A38") (pintype "passive"))
    )
    (net (code "311") (name "/ETHA_TXCTL") (class "Default")
      (node (ref "HT2") (pin "B37") (pinfunction "B37_B37") (pintype "passive"))
    )
    (net (code "312") (name "/ETHA_TXD0") (class "Default")
      (node (ref "HT2") (pin "B32") (pinfunction "B32_B32") (pintype "passive"))
    )
    (net (code "313") (name "/ETHA_TXD1") (class "Default")
      (node (ref "HT2") (pin "B33") (pinfunction "B33_B33") (pintype "passive"))
    )
    (net (code "314") (name "/ETHA_TXD2") (class "Default")
      (node (ref "HT2") (pin "A39") (pinfunction "A39_A39") (pintype "passive"))
    )
    (net (code "315") (name "/ETHA_TXD3") (class "Default")
      (node (ref "HT2") (pin "B36") (pinfunction "B36_B36") (pintype "passive"))
    )
    (net (code "316") (name "/ETHB_MDC") (class "Default")
      (node (ref "HT2") (pin "A19") (pinfunction "A19_A19") (pintype "passive"))
    )
    (net (code "317") (name "/ETHB_MDIO") (class "Default")
      (node (ref "HT2") (pin "A20") (pinfunction "A20_A20") (pintype "passive"))
    )
    (net (code "318") (name "/ETHB_RXCK") (class "Default")
      (node (ref "HT2") (pin "B30") (pinfunction "B30_B30") (pintype "passive"))
    )
    (net (code "319") (name "/ETHB_RXCTL") (class "Default")
      (node (ref "HT2") (pin "B14") (pinfunction "B14_B14") (pintype "passive"))
    )
    (net (code "320") (name "/ETHB_RXD0") (class "Default")
      (node (ref "HT2") (pin "B15") (pinfunction "B15_B15") (pintype "passive"))
    )
    (net (code "321") (name "/ETHB_RXD1") (class "Default")
      (node (ref "HT2") (pin "B16") (pinfunction "B16_B16") (pintype "passive"))
    )
    (net (code "322") (name "/ETHB_RXD2") (class "Default")
      (node (ref "HT2") (pin "B17") (pinfunction "B17_B17") (pintype "passive"))
    )
    (net (code "323") (name "/ETHB_RXD3") (class "Default")
      (node (ref "HT2") (pin "B18") (pinfunction "B18_B18") (pintype "passive"))
    )
    (net (code "324") (name "/ETHB_TXCK") (class "Default")
      (node (ref "HT2") (pin "B21") (pinfunction "B21_B21") (pintype "passive"))
    )
    (net (code "325") (name "/ETHB_TXCTL") (class "Default")
      (node (ref "HT2") (pin "B25") (pinfunction "B25_B25") (pintype "passive"))
    )
    (net (code "326") (name "/ETHB_TXD0") (class "Default")
      (node (ref "HT2") (pin "B19") (pinfunction "B19_B19") (pintype "passive"))
    )
    (net (code "327") (name "/ETHB_TXD1") (class "Default")
      (node (ref "HT2") (pin "B20") (pinfunction "B20_B20") (pintype "passive"))
    )
    (net (code "328") (name "/ETHB_TXD2") (class "Default")
      (node (ref "HT2") (pin "B23") (pinfunction "B23_B23") (pintype "passive"))
    )
    (net (code "329") (name "/ETHB_TXD3") (class "Default")
      (node (ref "HT2") (pin "B24") (pinfunction "B24_B24") (pintype "passive"))
    )
    (net (code "330") (name "/ETH_MDC") (class "Default")
      (node (ref "HT2") (pin "B38") (pinfunction "B38_B38") (pintype "passive"))
    )
    (net (code "331") (name "/ETH_MDIO") (class "Default")
      (node (ref "HT2") (pin "B39") (pinfunction "B39_B39") (pintype "passive"))
    )
    (net (code "343") (name "/H1_HPD") (class "Default")
      (node (ref "HT1") (pin "A60") (pinfunction "A60_A60") (pintype "passive"))
    )
    (net (code "347") (name "/HDMI1_FPGA_CLK_N") (class "Default")
      (node (ref "HT2") (pin "A36") (pinfunction "A36_A36") (pintype "passive"))
    )
    (net (code "348") (name "/HDMI1_FPGA_CLK_P") (class "Default")
      (node (ref "HT2") (pin "A37") (pinfunction "A37_A37") (pintype "passive"))
    )
    (net (code "349") (name "/HDMI1_FPGA_D0_N") (class "Default")
      (node (ref "HT2") (pin "A29") (pinfunction "A29_A29") (pintype "passive"))
    )
    (net (code "350") (name "/HDMI1_FPGA_D0_P") (class "Default")
      (node (ref "HT2") (pin "A30") (pinfunction "A30_A30") (pintype "passive"))
    )
    (net (code "351") (name "/HDMI1_FPGA_D1_N") (class "Default")
      (node (ref "HT2") (pin "A32") (pinfunction "A32_A32") (pintype "passive"))
    )
    (net (code "352") (name "/HDMI1_FPGA_D1_P") (class "Default")
      (node (ref "HT2") (pin "A33") (pinfunction "A33_A33") (pintype "passive"))
    )
    (net (code "353") (name "/HDMI1_FPGA_D2_N") (class "Default")
      (node (ref "HT2") (pin "A34") (pinfunction "A34_A34") (pintype "passive"))
    )
    (net (code "354") (name "/HDMI1_FPGA_D2_P") (class "Default")
      (node (ref "HT2") (pin "A35") (pinfunction "A35_A35") (pintype "passive"))
    )
    (net (code "360") (name "/LED5") (class "Default")
      (node (ref "HT2") (pin "A41") (pinfunction "A41_A41") (pintype "passive"))
    )
    (net (code "379") (name "/MGT112CLK0_N") (class "Default")
      (node (ref "HT3") (pin "B49") (pinfunction "B49_B49") (pintype "passive"))
    )
    (net (code "380") (name "/MGT112CLK0_P") (class "Default")
      (node (ref "HT3") (pin "B50") (pinfunction "B50_B50") (pintype "passive"))
    )
    (net (code "401") (name "/OTG-ID") (class "Default")
      (node (ref "HT2") (pin "A57") (pinfunction "A57_A57") (pintype "passive"))
    )
    (net (code "402") (name "/OTG-RESETN") (class "Default")
      (node (ref "HT2") (pin "B48") (pinfunction "B48_B48") (pintype "passive"))
    )
    (net (code "403") (name "/PCIE_CLK_N") (class "Default")
      (node (ref "HT3") (pin "A49") (pinfunction "A49_A49") (pintype "passive"))
    )
    (net (code "404") (name "/PCIE_CLK_P") (class "Default")
      (node (ref "HT3") (pin "A50") (pinfunction "A50_A50") (pintype "passive"))
    )
    (net (code "405") (name "/PCIE_PG") (class "Default")
      (node (ref "HT2") (pin "A27") (pinfunction "A27_A27") (pintype "passive"))
    )
    (net (code "406") (name "/PCIE_RX0_N") (class "Default")
      (node (ref "HT3") (pin "B37") (pinfunction "B37_B37") (pintype "passive"))
    )
    (net (code "407") (name "/PCIE_RX0_P") (class "Default")
      (node (ref "HT3") (pin "B38") (pinfunction "B38_B38") (pintype "passive"))
    )
    (net (code "408") (name "/PCIE_RX1_N") (class "Default")
      (node (ref "HT3") (pin "B40") (pinfunction "B40_B40") (pintype "passive"))
    )
    (net (code "409") (name "/PCIE_RX1_P") (class "Default")
      (node (ref "HT3") (pin "B41") (pinfunction "B41_B41") (pintype "passive"))
    )
    (net (code "410") (name "/PCIE_RX2_N") (class "Default")
      (node (ref "HT3") (pin "B43") (pinfunction "B43_B43") (pintype "passive"))
    )
    (net (code "411") (name "/PCIE_RX2_P") (class "Default")
      (node (ref "HT3") (pin "B44") (pinfunction "B44_B44") (pintype "passive"))
    )
    (net (code "412") (name "/PCIE_RX3_N") (class "Default")
      (node (ref "HT3") (pin "B46") (pinfunction "B46_B46") (pintype "passive"))
    )
    (net (code "413") (name "/PCIE_RX3_P") (class "Default")
      (node (ref "HT3") (pin "B47") (pinfunction "B47_B47") (pintype "passive"))
    )
    (net (code "414") (name "/PCIE_TX0_N") (class "Default")
      (node (ref "HT3") (pin "A37") (pinfunction "A37_A37") (pintype "passive"))
    )
    (net (code "415") (name "/PCIE_TX0_P") (class "Default")
      (node (ref "HT3") (pin "A38") (pinfunction "A38_A38") (pintype "passive"))
    )
    (net (code "416") (name "/PCIE_TX1_N") (class "Default")
      (node (ref "HT3") (pin "A40") (pinfunction "A40_A40") (pintype "passive"))
    )
    (net (code "417") (name "/PCIE_TX1_P") (class "Default")
      (node (ref "HT3") (pin "A41") (pinfunction "A41_A41") (pintype "passive"))
    )
    (net (code "418") (name "/PCIE_TX2_N") (class "Default")
      (node (ref "HT3") (pin "A43") (pinfunction "A43_A43") (pintype "passive"))
    )
    (net (code "419") (name "/PCIE_TX2_P") (class "Default")
      (node (ref "HT3") (pin "A44") (pinfunction "A44_A44") (pintype "passive"))
    )
    (net (code "420") (name "/PCIE_TX3_N") (class "Default")
      (node (ref "HT3") (pin "A46") (pinfunction "A46_A46") (pintype "passive"))
    )
    (net (code "421") (name "/PCIE_TX3_P") (class "Default")
      (node (ref "HT3") (pin "A47") (pinfunction "A47_A47") (pintype "passive"))
    )
    (net (code "422") (name "/PS_RST") (class "Default")
      (node (ref "HT2") (pin "A45") (pinfunction "A45_A45") (pintype "passive"))
    )
    (net (code "427") (name "/SATA1_RX_N") (class "Default")
      (node (ref "HT3") (pin "B31") (pinfunction "B31_B31") (pintype "passive"))
    )
    (net (code "428") (name "/SATA1_RX_P") (class "Default")
      (node (ref "HT3") (pin "B32") (pinfunction "B32_B32") (pintype "passive"))
    )
    (net (code "429") (name "/SATA1_TX_N") (class "Default")
      (node (ref "HT3") (pin "A31") (pinfunction "A31_A31") (pintype "passive"))
    )
    (net (code "430") (name "/SATA1_TX_P") (class "Default")
      (node (ref "HT3") (pin "A32") (pinfunction "A32_A32") (pintype "passive"))
    )
    (net (code "431") (name "/SATA2_RX_N") (class "Default")
      (node (ref "HT3") (pin "B34") (pinfunction "B34_B34") (pintype "passive"))
    )
    (net (code "432") (name "/SATA2_RX_P") (class "Default")
      (node (ref "HT3") (pin "B35") (pinfunction "B35_B35") (pintype "passive"))
    )
    (net (code "433") (name "/SATA2_TX_N") (class "Default")
      (node (ref "HT3") (pin "A34") (pinfunction "A34_A34") (pintype "passive"))
    )
    (net (code "434") (name "/SATA2_TX_P") (class "Default")
      (node (ref "HT3") (pin "A35") (pinfunction "A35_A35") (pintype "passive"))
    )
    (net (code "435") (name "/SD_CD_L") (class "Default")
      (node (ref "HT2") (pin "A50") (pinfunction "A50_A50") (pintype "passive"))
      (node (ref "J1") (pin "9") (pinfunction "9_9") (pintype "passive"))
    )
    (net (code "436") (name "/SFPA_RD_N") (class "Default")
      (node (ref "HT3") (pin "B28") (pinfunction "B28_B28") (pintype "passive"))
    )
    (net (code "437") (name "/SFPA_RD_P") (class "Default")
      (node (ref "HT3") (pin "B29") (pinfunction "B29_B29") (pintype "passive"))
    )
    (net (code "438") (name "/SFPA_TD_N") (class "Default")
      (node (ref "HT3") (pin "A28") (pinfunction "A28_A28") (pintype "passive"))
    )
    (net (code "439") (name "/SFPA_TD_P") (class "Default")
      (node (ref "HT3") (pin "A29") (pinfunction "A29_A29") (pintype "passive"))
    )
    (net (code "440") (name "/SFPB_RD_N") (class "Default")
      (node (ref "HT3") (pin "B25") (pinfunction "B25_B25") (pintype "passive"))
    )
    (net (code "441") (name "/SFPB_RD_P") (class "Default")
      (node (ref "HT3") (pin "B26") (pinfunction "B26_B26") (pintype "passive"))
    )
    (net (code "442") (name "/SFPB_TD_N") (class "Default")
      (node (ref "HT3") (pin "A25") (pinfunction "A25_A25") (pintype "passive"))
    )
    (net (code "443") (name "/SFPB_TD_P") (class "Default")
      (node (ref "HT3") (pin "A26") (pinfunction "A26_A26") (pintype "passive"))
    )
    (net (code "446") (name "/TCK_JTAG") (class "Default")
      (node (ref "HT3") (pin "A5") (pinfunction "A5_A5") (pintype "passive"))
      (node (ref "JTAG") (pin "1") (pinfunction "1_1") (pintype "passive"))
      (node (ref "U1") (pin "1") (pinfunction "IN1_1") (pintype "input"))
      (node (ref "U1") (pin "10") (pinfunction "OUT1_10") (pintype "output"))
    )
    (net (code "447") (name "/TDI_JTAG") (class "Default")
      (node (ref "HT3") (pin "A7") (pinfunction "A7_A7") (pintype "passive"))
      (node (ref "JTAG") (pin "9") (pinfunction "9_9") (pintype "passive"))
      (node (ref "U1") (pin "5") (pinfunction "IN4_5") (pintype "input"))
      (node (ref "U1") (pin "6") (pinfunction "OUT4_6") (pintype "output"))
    )
    (net (code "448") (name "/TDO_JTAG") (class "Default")
      (node (ref "HT3") (pin "A8") (pinfunction "A8_A8") (pintype "passive"))
      (node (ref "JTAG") (pin "3") (pinfunction "3_3") (pintype "passive"))
      (node (ref "U1") (pin "2") (pinfunction "IN2_2") (pintype "input"))
      (node (ref "U1") (pin "9") (pinfunction "OUT2_9") (pintype "output"))
    )
    (net (code "449") (name "/TF_CLK") (class "Default")
      (node (ref "HT2") (pin "A53") (pinfunction "A53_A53") (pintype "passive"))
      (node (ref "J1") (pin "5") (pinfunction "5_5") (pintype "passive"))
    )
    (net (code "450") (name "/TF_CMD") (class "Default")
      (node (ref "HT2") (pin "A54") (pinfunction "A54_A54") (pintype "passive"))
      (node (ref "J1") (pin "3") (pinfunction "3_3") (pintype "passive"))
    )
    (net (code "451") (name "/TF_DAT0") (class "Default")
      (node (ref "HT2") (pin "A52") (pinfunction "A52_A52") (pintype "passive"))
      (node (ref "J1") (pin "7") (pinfunction "7_7") (pintype "passive"))
    )
    (net (code "452") (name "/TF_DAT1") (class "Default")
      (node (ref "HT2") (pin "A51") (pinfunction "A51_A51") (pintype "passive"))
      (node (ref "J1") (pin "8") (pinfunction "8_8") (pintype "passive"))
    )
    (net (code "453") (name "/TF_DAT2") (class "Default")
      (node (ref "HT2") (pin "A56") (pinfunction "A56_A56") (pintype "passive"))
      (node (ref "J1") (pin "1") (pinfunction "1_1") (pintype "passive"))
    )
    (net (code "454") (name "/TF_DAT3") (class "Default")
      (node (ref "HT2") (pin "A55") (pinfunction "A55_A55") (pintype "passive"))
      (node (ref "J1") (pin "2") (pinfunction "2_2") (pintype "passive"))
    )
    (net (code "455") (name "/TMS_JTAG") (class "Default")
      (node (ref "HT3") (pin "A6") (pinfunction "A6_A6") (pintype "passive"))
      (node (ref "JTAG") (pin "5") (pinfunction "5_5") (pintype "passive"))
      (node (ref "U1") (pin "4") (pinfunction "IN3_4") (pintype "input"))
      (node (ref "U1") (pin "7") (pinfunction "OUT3_7") (pintype "output"))
    )
    (net (code "458") (name "/UART_RXD") (class "Default")
      (node (ref "HT2") (pin "B44") (pinfunction "B44_B44") (pintype "passive"))
    )
    (net (code "459") (name "/UART_TXD") (class "Default")
      (node (ref "HT2") (pin "B43") (pinfunction "B43_B43") (pintype "passive"))
    )
    (net (code "460") (name "/USB5V0") (class "Default")
      (node (ref "HT2") (pin "B46") (pinfunction "B46_B46") (pintype "passive"))
      (node (ref "HT2") (pin "B47") (pinfunction "B47_B47") (pintype "passive"))
    )
    (net (code "461") (name "/USB_5V") (class "Default")
      (node (ref "HT3") (pin "A10") (pinfunction "A10_A10") (pintype "passive"))
    )
    (net (code "462") (name "/USB_PHY_N") (class "Default")
      (node (ref "HT2") (pin "A59") (pinfunction "A59_A59") (pintype "passive"))
    )
    (net (code "463") (name "/USB_PHY_P") (class "Default")
      (node (ref "HT2") (pin "A60") (pinfunction "A60_A60") (pintype "passive"))
    )
    (net (code "466") (name "/VCC1V8") (class "Default")
      (node (ref "FEP1") (pin "C28") (pinfunction "C28_C28") (pintype "passive"))
      (node (ref "FEP1") (pin "C29") (pinfunction "C29_C29") (pintype "passive"))
    )
    (net (code "467") (name "/VCC2V5") (class "Default")
      (node (ref "FEP1") (pin "A28") (pinfunction "A28_A28") (pintype "passive"))
      (node (ref "FEP1") (pin "A29") (pinfunction "A29_A29") (pintype "passive"))
    )
    (net (code "490") (name "5V_IN") (class "Default")
      (node (ref "FEP1") (pin "A1") (pinfunction "A1_A1") (pintype "passive"))
      (node (ref "FEP1") (pin "B1") (pinfunction "B1_B1") (pintype "passive"))
      (node (ref "FEP1") (pin "C1") (pinfunction "C1_C1") (pintype "passive"))
      (node (ref "FEP1") (pin "D1") (pinfunction "D1_D1") (pintype "passive"))
      (node (ref "HT1") (pin "A1") (pinfunction "A1_A1") (pintype "passive"))
      (node (ref "HT1") (pin "A2") (pinfunction "A2_A2") (pintype "passive"))
      (node (ref "HT1") (pin "B1") (pinfunction "B1_B1") (pintype "passive"))
      (node (ref "HT1") (pin "B2") (pinfunction "B2_B2") (pintype "passive"))
      (node (ref "HT2") (pin "A1") (pinfunction "A1_A1") (pintype "passive"))
      (node (ref "HT2") (pin "A2") (pinfunction "A2_A2") (pintype "passive"))
      (node (ref "HT2") (pin "B1") (pinfunction "B1_B1") (pintype "passive"))
      (node (ref "HT2") (pin "B2") (pinfunction "B2_B2") (pintype "passive"))
      (node (ref "HT3") (pin "A1") (pinfunction "A1_A1") (pintype "passive"))
      (node (ref "HT3") (pin "A2") (pinfunction "A2_A2") (pintype "passive"))
      (node (ref "HT3") (pin "B1") (pinfunction "B1_B1") (pintype "passive"))
      (node (ref "HT3") (pin "B2") (pinfunction "B2_B2") (pintype "passive"))
    )
    (net (code "491") (name "GND") (class "Default")
      (node (ref "C1") (pin "2") (pinfunction "2_2") (pintype "passive"))
      (node (ref "C2") (pin "1") (pinfunction "1_1") (pintype "passive"))
      (node (ref "FEP1") (pin "A12") (pinfunction "A12_A12") (pintype "passive"))
      (node (ref "FEP1") (pin "A2") (pinfunction "A2_A2") (pintype "passive"))
      (node (ref "FEP1") (pin "A21") (pinfunction "A21_A21") (pintype "passive"))
      (node (ref "FEP1") (pin "A3") (pinfunction "A3_A3") (pintype "passive"))
      (node (ref "FEP1") (pin "A30") (pinfunction "A30_A30") (pintype "passive"))
      (node (ref "FEP1") (pin "B12") (pinfunction "B12_B12") (pintype "passive"))
      (node (ref "FEP1") (pin "B2") (pinfunction "B2_B2") (pintype "passive"))
      (node (ref "FEP1") (pin "B21") (pinfunction "B21_B21") (pintype "passive"))
      (node (ref "FEP1") (pin "B3") (pinfunction "B3_B3") (pintype "passive"))
      (node (ref "FEP1") (pin "B30") (pinfunction "B30_B30") (pintype "passive"))
      (node (ref "FEP1") (pin "C12") (pinfunction "C12_C12") (pintype "passive"))
      (node (ref "FEP1") (pin "C2") (pinfunction "C2_C2") (pintype "passive"))
      (node (ref "FEP1") (pin "C21") (pinfunction "C21_C21") (pintype "passive"))
      (node (ref "FEP1") (pin "C3") (pinfunction "C3_C3") (pintype "passive"))
      (node (ref "FEP1") (pin "C30") (pinfunction "C30_C30") (pintype "passive"))
      (node (ref "FEP1") (pin "D12") (pinfunction "D12_D12") (pintype "passive"))
      (node (ref "FEP1") (pin "D2") (pinfunction "D2_D2") (pintype "passive"))
      (node (ref "FEP1") (pin "D21") (pinfunction "D21_D21") (pintype "passive"))
      (node (ref "FEP1") (pin "D3") (pinfunction "D3_D3") (pintype "passive"))
      (node (ref "FEP1") (pin "D30") (pinfunction "D30_D30") (pintype "passive"))
      (node (ref "FEP1") (pin "P1") (pinfunction "P1_P1") (pintype "passive"))
      (node (ref "FEP1") (pin "P2") (pinfunction "P2_P2") (pintype "passive"))
      (node (ref "HT1") (pin "A13") (pinfunction "A13_A13") (pintype "passive"))
      (node (ref "HT1") (pin "A22") (pinfunction "A22_A22") (pintype "passive"))
      (node (ref "HT1") (pin "A3") (pinfunction "A3_A3") (pintype "passive"))
      (node (ref "HT1") (pin "A31") (pinfunction "A31_A31") (pintype "passive"))
      (node (ref "HT1") (pin "A4") (pinfunction "A4_A4") (pintype "passive"))
      (node (ref "HT1") (pin "A40") (pinfunction "A40_A40") (pintype "passive"))
      (node (ref "HT1") (pin "A49") (pinfunction "A49_A49") (pintype "passive"))
      (node (ref "HT1") (pin "A58") (pinfunction "A58_A58") (pintype "passive"))
      (node (ref "HT1") (pin "B13") (pinfunction "B13_B13") (pintype "passive"))
      (node (ref "HT1") (pin "B22") (pinfunction "B22_B22") (pintype "passive"))
      (node (ref "HT1") (pin "B3") (pinfunction "B3_B3") (pintype "passive"))
      (node (ref "HT1") (pin "B31") (pinfunction "B31_B31") (pintype "passive"))
      (node (ref "HT1") (pin "B4") (pinfunction "B4_B4") (pintype "passive"))
      (node (ref "HT1") (pin "B40") (pinfunction "B40_B40") (pintype "passive"))
      (node (ref "HT1") (pin "B49") (pinfunction "B49_B49") (pintype "passive"))
      (node (ref "HT1") (pin "B58") (pinfunction "B58_B58") (pintype "passive"))
      (node (ref "HT2") (pin "A13") (pinfunction "A13_A13") (pintype "passive"))
      (node (ref "HT2") (pin "A22") (pinfunction "A22_A22") (pintype "passive"))
      (node (ref "HT2") (pin "A3") (pinfunction "A3_A3") (pintype "passive"))
      (node (ref "HT2") (pin "A31") (pinfunction "A31_A31") (pintype "passive"))
      (node (ref "HT2") (pin "A4") (pinfunction "A4_A4") (pintype "passive"))
      (node (ref "HT2") (pin "A40") (pinfunction "A40_A40") (pintype "passive"))
      (node (ref "HT2") (pin "A49") (pinfunction "A49_A49") (pintype "passive"))
      (node (ref "HT2") (pin "A58") (pinfunction "A58_A58") (pintype "passive"))
      (node (ref "HT2") (pin "B13") (pinfunction "B13_B13") (pintype "passive"))
      (node (ref "HT2") (pin "B22") (pinfunction "B22_B22") (pintype "passive"))
      (node (ref "HT2") (pin "B3") (pinfunction "B3_B3") (pintype "passive"))
      (node (ref "HT2") (pin "B31") (pinfunction "B31_B31") (pintype "passive"))
      (node (ref "HT2") (pin "B4") (pinfunction "B4_B4") (pintype "passive"))
      (node (ref "HT2") (pin "B40") (pinfunction "B40_B40") (pintype "passive"))
      (node (ref "HT2") (pin "B49") (pinfunction "B49_B49") (pintype "passive"))
      (node (ref "HT2") (pin "B58") (pinfunction "B58_B58") (pintype "passive"))
      (node (ref "HT3") (pin "A13") (pinfunction "A13_A13") (pintype "passive"))
      (node (ref "HT3") (pin "A24") (pinfunction "A24_A24") (pintype "passive"))
      (node (ref "HT3") (pin "A27") (pinfunction "A27_A27") (pintype "passive"))
      (node (ref "HT3") (pin "A3") (pinfunction "A3_A3") (pintype "passive"))
      (node (ref "HT3") (pin "A30") (pinfunction "A30_A30") (pintype "passive"))
      (node (ref "HT3") (pin "A33") (pinfunction "A33_A33") (pintype "passive"))
      (node (ref "HT3") (pin "A36") (pinfunction "A36_A36") (pintype "passive"))
      (node (ref "HT3") (pin "A39") (pinfunction "A39_A39") (pintype "passive"))
      (node (ref "HT3") (pin "A4") (pinfunction "A4_A4") (pintype "passive"))
      (node (ref "HT3") (pin "A42") (pinfunction "A42_A42") (pintype "passive"))
      (node (ref "HT3") (pin "A45") (pinfunction "A45_A45") (pintype "passive"))
      (node (ref "HT3") (pin "A48") (pinfunction "A48_A48") (pintype "passive"))
      (node (ref "HT3") (pin "B13") (pinfunction "B13_B13") (pintype "passive"))
      (node (ref "HT3") (pin "B15") (pinfunction "B15_B15") (pintype "passive"))
      (node (ref "HT3") (pin "B16") (pinfunction "B16_B16") (pintype "passive"))
      (node (ref "HT3") (pin "B20") (pinfunction "B20_B20") (pintype "passive"))
      (node (ref "HT3") (pin "B21") (pinfunction "B21_B21") (pintype "passive"))
      (node (ref "HT3") (pin "B24") (pinfunction "B24_B24") (pintype "passive"))
      (node (ref "HT3") (pin "B27") (pinfunction "B27_B27") (pintype "passive"))
      (node (ref "HT3") (pin "B3") (pinfunction "B3_B3") (pintype "passive"))
      (node (ref "HT3") (pin "B30") (pinfunction "B30_B30") (pintype "passive"))
      (node (ref "HT3") (pin "B33") (pinfunction "B33_B33") (pintype "passive"))
      (node (ref "HT3") (pin "B36") (pinfunction "B36_B36") (pintype "passive"))
      (node (ref "HT3") (pin "B39") (pinfunction "B39_B39") (pintype "passive"))
      (node (ref "HT3") (pin "B4") (pinfunction "B4_B4") (pintype "passive"))
      (node (ref "HT3") (pin "B42") (pinfunction "B42_B42") (pintype "passive"))
      (node (ref "HT3") (pin "B45") (pinfunction "B45_B45") (pintype "passive"))
      (node (ref "HT3") (pin "B48") (pinfunction "B48_B48") (pintype "passive"))
      (node (ref "HT3") (pin "B8") (pinfunction "B8_B8") (pintype "passive"))
      (node (ref "J1") (pin "0") (pinfunction "0_0") (pintype "passive"))
      (node (ref "J1") (pin "10") (pinfunction "10_10") (pintype "passive"))
      (node (ref "J1") (pin "11") (pinfunction "11_11") (pintype "passive"))
      (node (ref "J1") (pin "12") (pinfunction "12_12") (pintype "passive"))
      (node (ref "J1") (pin "6") (pinfunction "6_6") (pintype "passive"))
      (node (ref "J2") (pin "10") (pinfunction "GND_10") (pintype "power_in"))
      (node (ref "J2") (pin "15") (pinfunction "GND_15") (pintype "power_in"))
      (node (ref "J2") (pin "16") (pinfunction "GND_16") (pintype "power_in"))
      (node (ref "JTAG") (pin "10") (pinfunction "10_10") (pintype "passive"))
      (node (ref "JTAG") (pin "2") (pinfunction "2_2") (pintype "passive"))
      (node (ref "R2") (pin "2") (pinfunction "2_2") (pintype "passive"))
      (node (ref "U1") (pin "3") (pinfunction "GND_3") (pintype "power_in"))
      (node (ref "U1") (pin "8") (pinfunction "GND_8") (pintype "power_in"))
    )
    (net (code "492") (name "Net-(J2-TCT)") (class "Default")
      (node (ref "C2") (pin "2") (pinfunction "2_2") (pintype "passive"))
      (node (ref "J2") (pin "1") (pinfunction "TCT_1") (pintype "passive"))
    )
    (net (code "493") (name "VCC3V3") (class "Default")
      (node (ref "C1") (pin "1") (pinfunction "1_1") (pintype "passive"))
      (node (ref "FEP1") (pin "B28") (pinfunction "B28_B28") (pintype "passive"))
      (node (ref "FEP1") (pin "B29") (pinfunction "B29_B29") (pintype "passive"))
      (node (ref "HT3") (pin "B17") (pinfunction "B17_B17") (pintype "passive"))
      (node (ref "HT3") (pin "B18") (pinfunction "B18_B18") (pintype "passive"))
      (node (ref "HT3") (pin "B19") (pinfunction "B19_B19") (pintype "passive"))
      (node (ref "J1") (pin "4") (pinfunction "4_4") (pintype "passive"))
      (node (ref "J2") (pin "11") (pinfunction "LEDG+_11") (pintype "passive"))
      (node (ref "J2") (pin "14") (pinfunction "LEDY+_14") (pintype "passive"))
      (node (ref "JTAG") (pin "4") (pinfunction "4_4") (pintype "passive"))
    )
    (net (code "494") (name "unconnected-(HT1-PadC1)") (class "Default")
      (node (ref "HT1") (pin "C1") (pinfunction "C1_C1") (pintype "passive"))
    )
    (net (code "495") (name "unconnected-(HT1-PadC2)") (class "Default")
      (node (ref "HT1") (pin "C2") (pinfunction "C2_C2") (pintype "passive"))
    )
    (net (code "496") (name "unconnected-(HT2-PadA15)") (class "Default")
      (node (ref "HT2") (pin "A15") (pinfunction "A15_A15") (pintype "passive"))
    )
    (net (code "497") (name "unconnected-(HT2-PadA17)") (class "Default")
      (node (ref "HT2") (pin "A17") (pinfunction "A17_A17") (pintype "passive"))
    )
    (net (code "498") (name "unconnected-(HT2-PadA23)") (class "Default")
      (node (ref "HT2") (pin "A23") (pinfunction "A23_A23") (pintype "passive"))
    )
    (net (code "499") (name "unconnected-(HT2-PadA25)") (class "Default")
      (node (ref "HT2") (pin "A25") (pinfunction "A25_A25") (pintype "passive"))
    )
    (net (code "500") (name "unconnected-(HT2-PadA43)") (class "Default")
      (node (ref "HT2") (pin "A43") (pinfunction "A43_A43") (pintype "passive"))
    )
    (net (code "501") (name "unconnected-(HT2-PadA44)") (class "Default")
      (node (ref "HT2") (pin "A44") (pinfunction "A44_A44") (pintype "passive"))
    )
    (net (code "502") (name "unconnected-(HT2-PadA46)") (class "Default")
      (node (ref "HT2") (pin "A46") (pinfunction "A46_A46") (pintype "passive"))
    )
    (net (code "503") (name "unconnected-(HT2-PadA47)") (class "Default")
      (node (ref "HT2") (pin "A47") (pinfunction "A47_A47") (pintype "passive"))
    )
    (net (code "504") (name "unconnected-(HT2-PadA48)") (class "Default")
      (node (ref "HT2") (pin "A48") (pinfunction "A48_A48") (pintype "passive"))
    )
    (net (code "505") (name "unconnected-(HT2-PadB45)") (class "Default")
      (node (ref "HT2") (pin "B45") (pinfunction "B45_B45") (pintype "passive"))
    )
    (net (code "506") (name "unconnected-(HT2-PadC1)") (class "Default")
      (node (ref "HT2") (pin "C1") (pinfunction "C1_C1") (pintype "passive"))
    )
    (net (code "507") (name "unconnected-(HT2-PadC2)") (class "Default")
      (node (ref "HT2") (pin "C2") (pinfunction "C2_C2") (pintype "passive"))
    )
    (net (code "508") (name "unconnected-(HT3-PadA9)") (class "Default")
      (node (ref "HT3") (pin "A9") (pinfunction "A9_A9") (pintype "passive"))
    )
    (net (code "509") (name "unconnected-(HT3-PadA11)") (class "Default")
      (node (ref "HT3") (pin "A11") (pinfunction "A11_A11") (pintype "passive"))
    )
    (net (code "510") (name "unconnected-(HT3-PadA12)") (class "Default")
      (node (ref "HT3") (pin "A12") (pinfunction "A12_A12") (pintype "passive"))
    )
    (net (code "511") (name "unconnected-(HT3-PadA14)") (class "Default")
      (node (ref "HT3") (pin "A14") (pinfunction "A14_A14") (pintype "passive"))
    )
    (net (code "512") (name "unconnected-(HT3-PadA15)") (class "Default")
      (node (ref "HT3") (pin "A15") (pinfunction "A15_A15") (pintype "passive"))
    )
    (net (code "513") (name "unconnected-(HT3-PadA16)") (class "Default")
      (node (ref "HT3") (pin "A16") (pinfunction "A16_A16") (pintype "passive"))
    )
    (net (code "514") (name "unconnected-(HT3-PadA17)") (class "Default")
      (node (ref "HT3") (pin "A17") (pinfunction "A17_A17") (pintype "passive"))
    )
    (net (code "515") (name "unconnected-(HT3-PadA18)") (class "Default")
      (node (ref "HT3") (pin "A18") (pinfunction "A18_A18") (pintype "passive"))
    )
    (net (code "516") (name "unconnected-(HT3-PadA19)") (class "Default")
      (node (ref "HT3") (pin "A19") (pinfunction "A19_A19") (pintype "passive"))
    )
    (net (code "517") (name "unconnected-(HT3-PadA20)") (class "Default")
      (node (ref "HT3") (pin "A20") (pinfunction "A20_A20") (pintype "passive"))
    )
    (net (code "518") (name "unconnected-(HT3-PadA21)") (class "Default")
      (node (ref "HT3") (pin "A21") (pinfunction "A21_A21") (pintype "passive"))
    )
    (net (code "519") (name "unconnected-(HT3-PadA22)") (class "Default")
      (node (ref "HT3") (pin "A22") (pinfunction "A22_A22") (pintype "passive"))
    )
    (net (code "520") (name "unconnected-(HT3-PadA23)") (class "Default")
      (node (ref "HT3") (pin "A23") (pinfunction "A23_A23") (pintype "passive"))
    )
    (net (code "521") (name "unconnected-(HT3-PadB5)") (class "Default")
      (node (ref "HT3") (pin "B5") (pinfunction "B5_B5") (pintype "passive"))
    )
    (net (code "522") (name "unconnected-(HT3-PadB9)") (class "Default")
      (node (ref "HT3") (pin "B9") (pinfunction "B9_B9") (pintype "passive"))
    )
    (net (code "523") (name "unconnected-(HT3-PadB10)") (class "Default")
      (node (ref "HT3") (pin "B10") (pinfunction "B10_B10") (pintype "passive"))
    )
    (net (code "524") (name "unconnected-(HT3-PadB11)") (class "Default")
      (node (ref "HT3") (pin "B11") (pinfunction "B11_B11") (pintype "passive"))
    )
    (net (code "525") (name "unconnected-(HT3-PadB12)") (class "Default")
      (node (ref "HT3") (pin "B12") (pinfunction "B12_B12") (pintype "passive"))
    )
    (net (code "526") (name "unconnected-(HT3-PadB14)") (class "Default")
      (node (ref "HT3") (pin "B14") (pinfunction "B14_B14") (pintype "passive"))
    )
    (net (code "527") (name "unconnected-(HT3-PadB22)") (class "Default")
      (node (ref "HT3") (pin "B22") (pinfunction "B22_B22") (pintype "passive"))
    )
    (net (code "528") (name "unconnected-(HT3-PadB23)") (class "Default")
      (node (ref "HT3") (pin "B23") (pinfunction "B23_B23") (pintype "passive"))
    )
    (net (code "529") (name "unconnected-(HT3-PadC1)") (class "Default")
      (node (ref "HT3") (pin "C1") (pinfunction "C1_C1") (pintype "passive"))
    )
    (net (code "530") (name "unconnected-(HT3-PadC2)") (class "Default")
      (node (ref "HT3") (pin "C2") (pinfunction "C2_C2") (pintype "passive"))
    )
    (net (code "531") (name "unconnected-(JTAG-Pad6)") (class "Default")
      (node (ref "JTAG") (pin "6") (pinfunction "6_6") (pintype "passive"))
    )
    (net (code "532") (name "unconnected-(JTAG-Pad7)") (class "Default")
      (node (ref "JTAG") (pin "7") (pinfunction "7_7") (pintype "passive"))
    )
    (net (code "533") (name "unconnected-(JTAG-Pad8)") (class "Default")
      (node (ref "JTAG") (pin "8") (pinfunction "8_8") (pintype "passive"))
    )
  )
)
